# TS1108.net
KiCad netlist of a schematic drawn in EAGLE
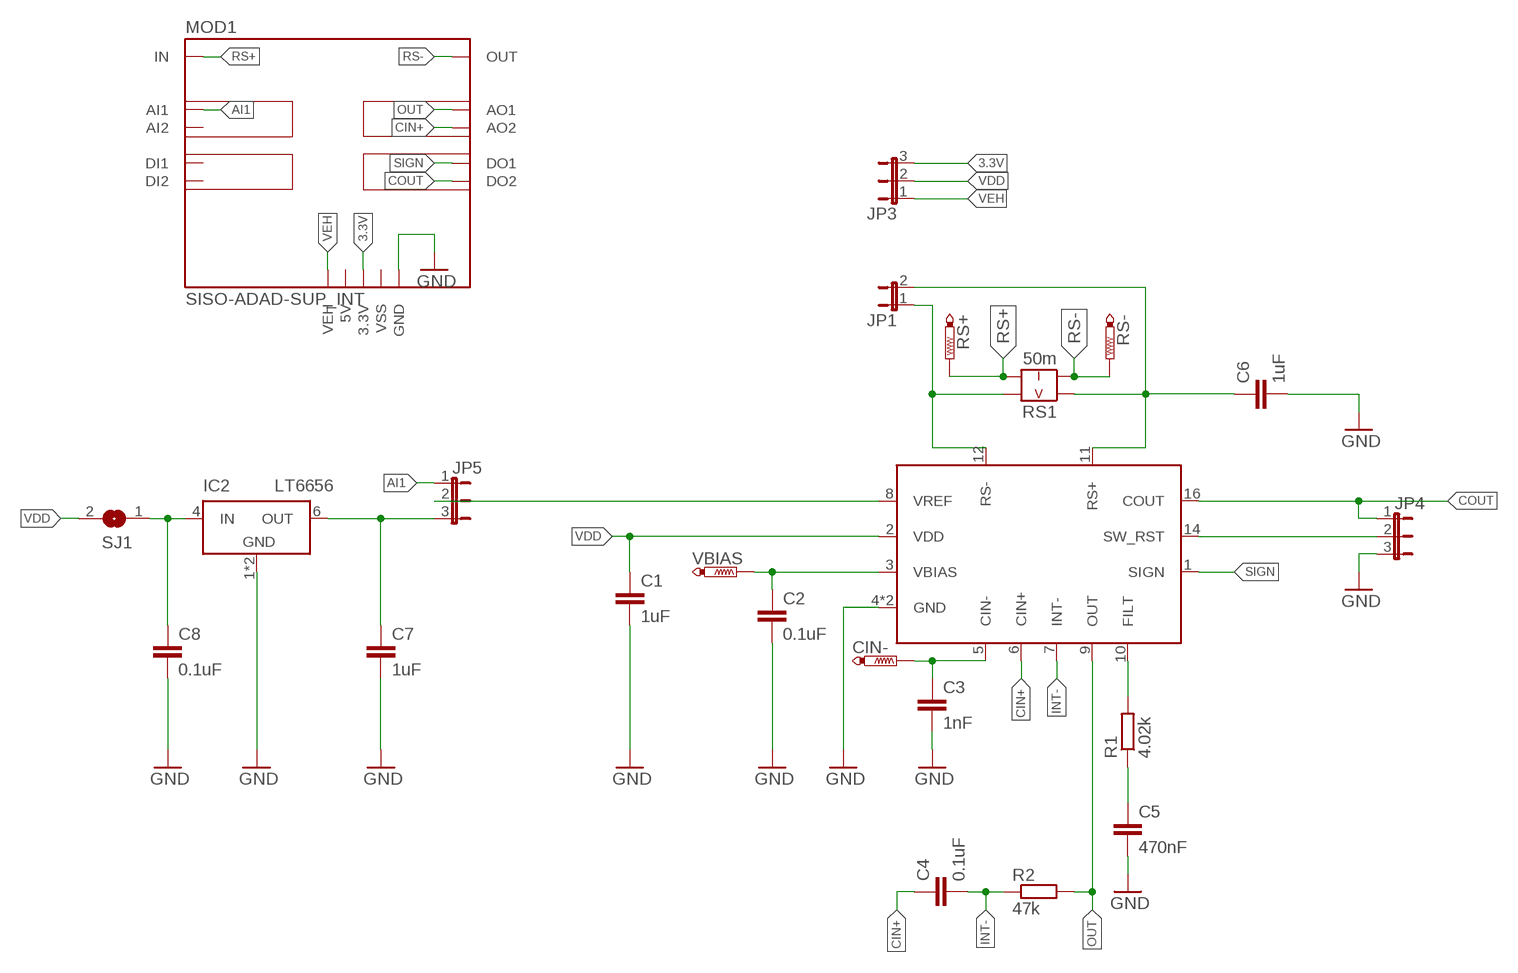
[diagram p0: schematic, sheet 1]

(export (version "E")
  (design (tool "Eeschema 10.0.6"))
  (components
    (comp (ref "C1")
      (value "1uF")
      (footprint "eagle-import:C0805K")
      (libsource (lib "eagle-import") (part "C-EUC0805K"))
    )
    (comp (ref "C2")
      (value "0.1uF")
      (footprint "eagle-import:C0805K")
      (libsource (lib "eagle-import") (part "C-EUC0805K"))
    )
    (comp (ref "C3")
      (value "1nF")
      (footprint "eagle-import:C0805K")
      (libsource (lib "eagle-import") (part "C-EUC0805K"))
    )
    (comp (ref "C4")
      (value "0.1uF")
      (footprint "eagle-import:C0805K")
      (libsource (lib "eagle-import") (part "C-EUC0805K"))
    )
    (comp (ref "C5")
      (value "470nF")
      (footprint "eagle-import:C0805K")
      (libsource (lib "eagle-import") (part "C-EUC0805K"))
    )
    (comp (ref "C6")
      (value "1uF")
      (footprint "eagle-import:C0805K")
      (libsource (lib "eagle-import") (part "C-EUC0805K"))
    )
    (comp (ref "C7")
      (value "1uF")
      (footprint "eagle-import:C0805K")
      (libsource (lib "eagle-import") (part "C-EUC0805K"))
    )
    (comp (ref "C8")
      (value "0.1uF")
      (footprint "eagle-import:C0805K")
      (libsource (lib "eagle-import") (part "C-EUC0805K"))
    )
    (comp (ref "CIN-")
      (value "PTR1B1,27")
      (footprint "eagle-import:B1,27")
      (libsource (lib "eagle-import") (part "PTR1B1,27"))
    )
    (comp (ref "IC1")
      (value "TS1108")
      (footprint "eagle-import:LFCSP16_WQ_CP-16-33")
      (libsource (lib "eagle-import") (part "TS1108"))
    )
    (comp (ref "IC2")
      (value "LT6656")
      (footprint "eagle-import:TSOT23-6")
      (libsource (lib "eagle-import") (part "LT6656"))
    )
    (comp (ref "JP1")
      (value "JP1E")
      (footprint "eagle-import:JP1")
      (libsource (lib "eagle-import") (part "JP1E"))
    )
    (comp (ref "JP3")
      (value "JP2E")
      (footprint "eagle-import:JP2")
      (libsource (lib "eagle-import") (part "JP2E"))
    )
    (comp (ref "JP4")
      (value "JP2E")
      (footprint "eagle-import:JP2")
      (libsource (lib "eagle-import") (part "JP2E"))
    )
    (comp (ref "JP5")
      (value "JP2E")
      (footprint "eagle-import:JP2")
      (libsource (lib "eagle-import") (part "JP2E"))
    )
    (comp (ref "MOD1")
      (value "SISO-ADAD-SUP_INT")
      (footprint "eagle-import:SISO-ADAD-SUP")
      (libsource (lib "eagle-import") (part "SISO-ADAD-SUP_INT"))
    )
    (comp (ref "R1")
      (value "4.02k")
      (footprint "eagle-import:R0805")
      (libsource (lib "eagle-import") (part "R-EU_R0805"))
    )
    (comp (ref "R2")
      (value "47k")
      (footprint "eagle-import:R0805")
      (libsource (lib "eagle-import") (part "R-EU_R0805"))
    )
    (comp (ref "RS+")
      (value "PTR1B1,27")
      (footprint "eagle-import:B1,27")
      (libsource (lib "eagle-import") (part "PTR1B1,27"))
    )
    (comp (ref "RS-")
      (value "PTR1B1,27")
      (footprint "eagle-import:B1,27")
      (libsource (lib "eagle-import") (part "PTR1B1,27"))
    )
    (comp (ref "RS1")
      (value "50m")
      (footprint "eagle-import:LVK12")
      (libsource (lib "eagle-import") (part "LVK_SERIESR1206"))
    )
    (comp (ref "SJ1") (value "SJ") (footprint "eagle-import:SJ") (libsource (lib "eagle-import") (part "SJ")))
    (comp (ref "VBIAS")
      (value "PTR1B1,27")
      (footprint "eagle-import:B1,27")
      (libsource (lib "eagle-import") (part "PTR1B1,27"))
    )
  )
  (nets
    (net (code "1") (name "/5V") (class "Default")
      (node (ref "MOD1") (pin "5V") (pinfunction "5V_5V") (pintype "power_in"))
    )
    (net (code "2") (name "/VSS") (class "Default")
      (node (ref "MOD1") (pin "VSS") (pinfunction "VSS_VSS") (pintype "power_in"))
    )
    (net (code "3") (name "3.3V") (class "Default")
      (node (ref "JP3") (pin "3") (pinfunction "3_3") (pintype "passive"))
      (node (ref "MOD1") (pin "3.3V") (pinfunction "3.3V_3.3V") (pintype "power_in"))
    )
    (net (code "4") (name "AI1") (class "Default")
      (node (ref "JP5") (pin "1") (pinfunction "1_1") (pintype "passive"))
      (node (ref "MOD1") (pin "AI1") (pinfunction "AI1_AI1") (pintype "output"))
    )
    (net (code "5") (name "CIN+") (class "Default")
      (node (ref "C4") (pin "1") (pinfunction "1_1") (pintype "passive"))
      (node (ref "IC1") (pin "6") (pinfunction "CIN+_6") (pintype "bidirectional"))
      (node (ref "MOD1") (pin "AO2") (pinfunction "AO2_AO2") (pintype "input"))
    )
    (net (code "6") (name "COUT") (class "Default")
      (node (ref "IC1") (pin "16") (pinfunction "COUT_16") (pintype "bidirectional"))
      (node (ref "JP4") (pin "1") (pinfunction "1_1") (pintype "passive"))
      (node (ref "MOD1") (pin "DO2") (pinfunction "DO2_DO2") (pintype "input"))
    )
    (net (code "7") (name "GND") (class "Default")
      (node (ref "C1") (pin "2") (pinfunction "2_2") (pintype "passive"))
      (node (ref "C2") (pin "2") (pinfunction "2_2") (pintype "passive"))
      (node (ref "C3") (pin "2") (pinfunction "2_2") (pintype "passive"))
      (node (ref "C5") (pin "2") (pinfunction "2_2") (pintype "passive"))
      (node (ref "C6") (pin "2") (pinfunction "2_2") (pintype "passive"))
      (node (ref "C7") (pin "2") (pinfunction "2_2") (pintype "passive"))
      (node (ref "C8") (pin "2") (pinfunction "2_2") (pintype "passive"))
      (node (ref "IC1") (pin "4") (pinfunction "GND_4") (pintype "power_in"))
      (node (ref "IC1") (pin "EXP") (pinfunction "GND_EXP") (pintype "power_in"))
      (node (ref "IC2") (pin "1") (pinfunction "GND_1") (pintype "power_in"))
      (node (ref "IC2") (pin "2") (pinfunction "GND_2") (pintype "power_in"))
      (node (ref "JP4") (pin "3") (pinfunction "3_3") (pintype "passive"))
      (node (ref "MOD1") (pin "GND1") (pinfunction "GND_GND1") (pintype "power_in"))
      (node (ref "MOD1") (pin "GND2") (pinfunction "GND_GND2") (pintype "power_in"))
      (node (ref "MOD1") (pin "GND3") (pinfunction "GND_GND3") (pintype "power_in"))
      (node (ref "MOD1") (pin "GND4") (pinfunction "GND_GND4") (pintype "power_in"))
    )
    (net (code "8") (name "INT-") (class "Default")
      (node (ref "C4") (pin "2") (pinfunction "2_2") (pintype "passive"))
      (node (ref "IC1") (pin "7") (pinfunction "INT-_7") (pintype "bidirectional"))
      (node (ref "R2") (pin "1") (pinfunction "1_1") (pintype "passive"))
    )
    (net (code "9") (name "Net-(C5-Pad1)") (class "Default")
      (node (ref "C5") (pin "1") (pinfunction "1_1") (pintype "passive"))
      (node (ref "R1") (pin "1") (pinfunction "1_1") (pintype "passive"))
    )
    (net (code "10") (name "Net-(IC1-CIN-)") (class "Default")
      (node (ref "C3") (pin "1") (pinfunction "1_1") (pintype "passive"))
      (node (ref "CIN-") (pin "TP") (pinfunction "TP_TP") (pintype "input"))
      (node (ref "IC1") (pin "5") (pinfunction "CIN-_5") (pintype "bidirectional"))
    )
    (net (code "11") (name "Net-(IC1-FILT)") (class "Default")
      (node (ref "IC1") (pin "10") (pinfunction "FILT_10") (pintype "bidirectional"))
      (node (ref "R1") (pin "2") (pinfunction "2_2") (pintype "passive"))
    )
    (net (code "12") (name "Net-(IC1-RS+)") (class "Default")
      (node (ref "C6") (pin "1") (pinfunction "1_1") (pintype "passive"))
      (node (ref "IC1") (pin "11") (pinfunction "RS+_11") (pintype "bidirectional"))
      (node (ref "JP1") (pin "2") (pinfunction "2_2") (pintype "passive"))
      (node (ref "RS1") (pin "V1") (pinfunction "V1_V1") (pintype "passive"))
    )
    (net (code "13") (name "Net-(IC1-RS-)") (class "Default")
      (node (ref "IC1") (pin "12") (pinfunction "RS-_12") (pintype "bidirectional"))
      (node (ref "JP1") (pin "1") (pinfunction "1_1") (pintype "passive"))
      (node (ref "RS1") (pin "V2") (pinfunction "V2_V2") (pintype "passive"))
    )
    (net (code "14") (name "Net-(IC1-SW_RST)") (class "Default")
      (node (ref "IC1") (pin "14") (pinfunction "SW_RST_14") (pintype "bidirectional"))
      (node (ref "JP4") (pin "2") (pinfunction "2_2") (pintype "passive"))
    )
    (net (code "15") (name "Net-(IC1-VBIAS)") (class "Default")
      (node (ref "C2") (pin "1") (pinfunction "1_1") (pintype "passive"))
      (node (ref "IC1") (pin "3") (pinfunction "VBIAS_3") (pintype "bidirectional"))
      (node (ref "VBIAS") (pin "TP") (pinfunction "TP_TP") (pintype "input"))
    )
    (net (code "16") (name "Net-(IC1-VREF)") (class "Default")
      (node (ref "IC1") (pin "8") (pinfunction "VREF_8") (pintype "power_in"))
      (node (ref "JP5") (pin "2") (pinfunction "2_2") (pintype "passive"))
    )
    (net (code "17") (name "Net-(IC2-IN)") (class "Default")
      (node (ref "C8") (pin "1") (pinfunction "1_1") (pintype "passive"))
      (node (ref "IC2") (pin "4") (pinfunction "IN_4") (pintype "input"))
      (node (ref "SJ1") (pin "1") (pinfunction "1_1") (pintype "passive"))
    )
    (net (code "18") (name "Net-(IC2-OUT)") (class "Default")
      (node (ref "C7") (pin "1") (pinfunction "1_1") (pintype "passive"))
      (node (ref "IC2") (pin "6") (pinfunction "OUT_6") (pintype "output"))
      (node (ref "JP5") (pin "3") (pinfunction "3_3") (pintype "passive"))
    )
    (net (code "19") (name "OUT") (class "Default")
      (node (ref "IC1") (pin "9") (pinfunction "OUT_9") (pintype "bidirectional"))
      (node (ref "MOD1") (pin "AO1") (pinfunction "AO1_AO1") (pintype "input"))
      (node (ref "R2") (pin "2") (pinfunction "2_2") (pintype "passive"))
    )
    (net (code "20") (name "RS+") (class "Default")
      (node (ref "MOD1") (pin "IN1") (pinfunction "IN_IN1") (pintype "output"))
      (node (ref "MOD1") (pin "IN2") (pinfunction "IN_IN2") (pintype "output"))
      (node (ref "MOD1") (pin "IN3") (pinfunction "IN_IN3") (pintype "output"))
      (node (ref "MOD1") (pin "IN4") (pinfunction "IN_IN4") (pintype "output"))
      (node (ref "RS+") (pin "TP") (pinfunction "TP_TP") (pintype "input"))
      (node (ref "RS1") (pin "I2") (pinfunction "I2_I2") (pintype "passive"))
    )
    (net (code "21") (name "RS-") (class "Default")
      (node (ref "MOD1") (pin "OUT1_1") (pinfunction "OUT_OUT1_1") (pintype "input"))
      (node (ref "MOD1") (pin "OUT1_2") (pinfunction "OUT_OUT1_2") (pintype "input"))
      (node (ref "MOD1") (pin "OUT1_3") (pinfunction "OUT_OUT1_3") (pintype "input"))
      (node (ref "MOD1") (pin "OUT1_4") (pinfunction "OUT_OUT1_4") (pintype "input"))
      (node (ref "RS-") (pin "TP") (pinfunction "TP_TP") (pintype "input"))
      (node (ref "RS1") (pin "I1") (pinfunction "I1_I1") (pintype "passive"))
    )
    (net (code "22") (name "SIGN") (class "Default")
      (node (ref "IC1") (pin "1") (pinfunction "SIGN_1") (pintype "bidirectional"))
      (node (ref "MOD1") (pin "DO1") (pinfunction "DO1_DO1") (pintype "input"))
    )
    (net (code "23") (name "VDD") (class "Default")
      (node (ref "C1") (pin "1") (pinfunction "1_1") (pintype "passive"))
      (node (ref "IC1") (pin "2") (pinfunction "VDD_2") (pintype "power_in"))
      (node (ref "JP3") (pin "2") (pinfunction "2_2") (pintype "passive"))
      (node (ref "SJ1") (pin "2") (pinfunction "2_2") (pintype "passive"))
    )
    (net (code "24") (name "VEH") (class "Default")
      (node (ref "JP3") (pin "1") (pinfunction "1_1") (pintype "passive"))
      (node (ref "MOD1") (pin "VEH") (pinfunction "VEH_VEH") (pintype "power_in"))
    )
    (net (code "25") (name "unconnected-(MOD1-PadAI2)") (class "Default")
      (node (ref "MOD1") (pin "AI2") (pinfunction "AI2_AI2") (pintype "output"))
    )
    (net (code "26") (name "unconnected-(MOD1-PadDI1)") (class "Default")
      (node (ref "MOD1") (pin "DI1") (pinfunction "DI1_DI1") (pintype "output"))
    )
    (net (code "27") (name "unconnected-(MOD1-PadDI2)") (class "Default")
      (node (ref "MOD1") (pin "DI2") (pinfunction "DI2_DI2") (pintype "output"))
    )
  )
)
